# MxxxRow.net
KiCad netlist of a schematic drawn in EAGLE
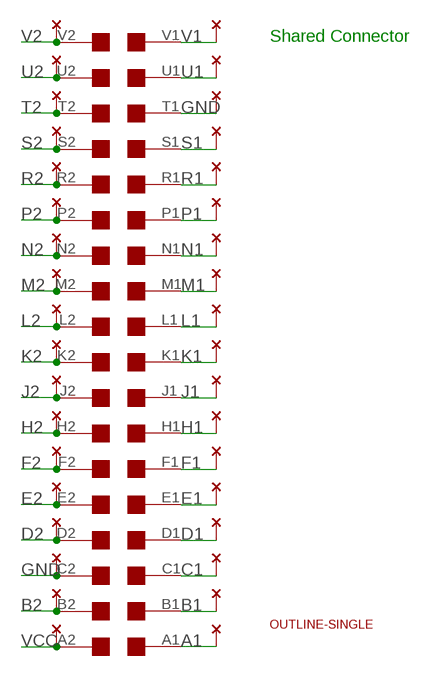
[diagram p0: schematic, sheet 1]
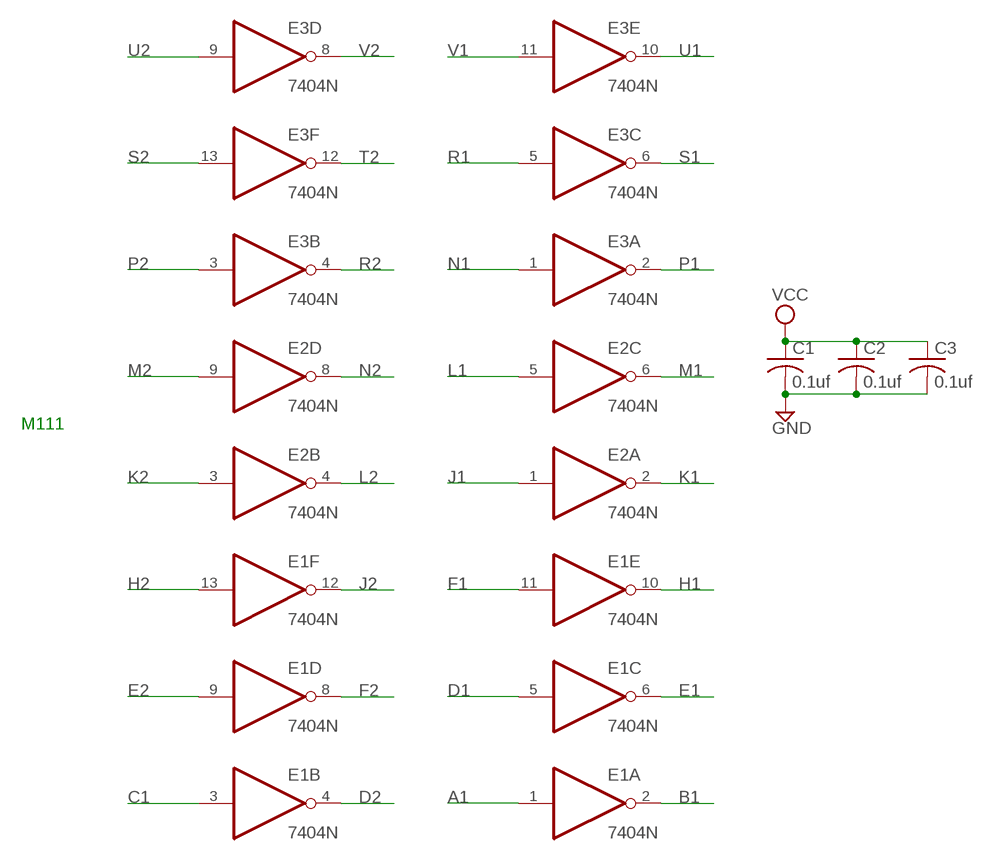
[diagram p1: schematic, sheet 2]
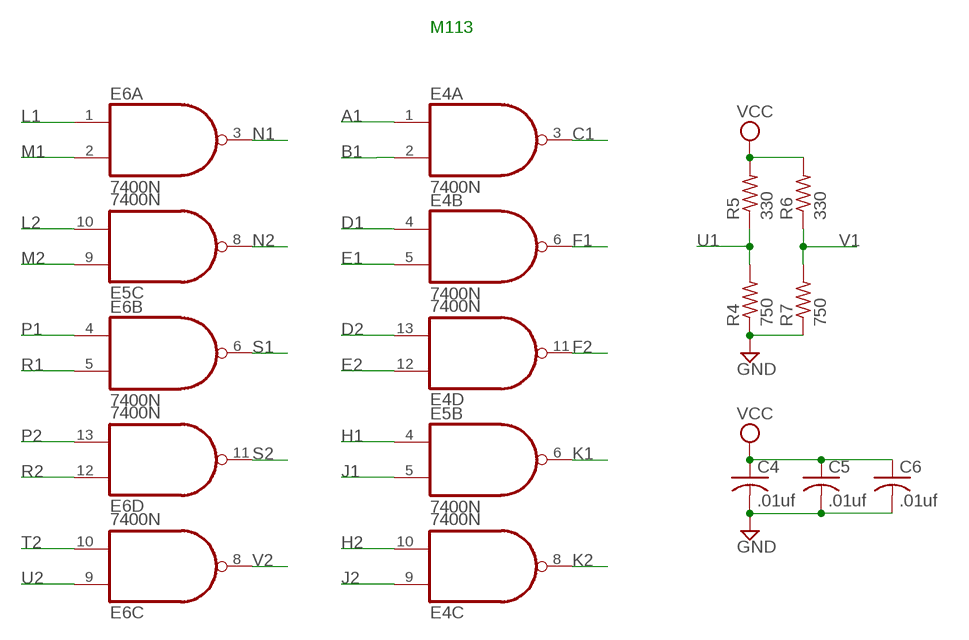
[diagram p2: schematic, sheet 3]
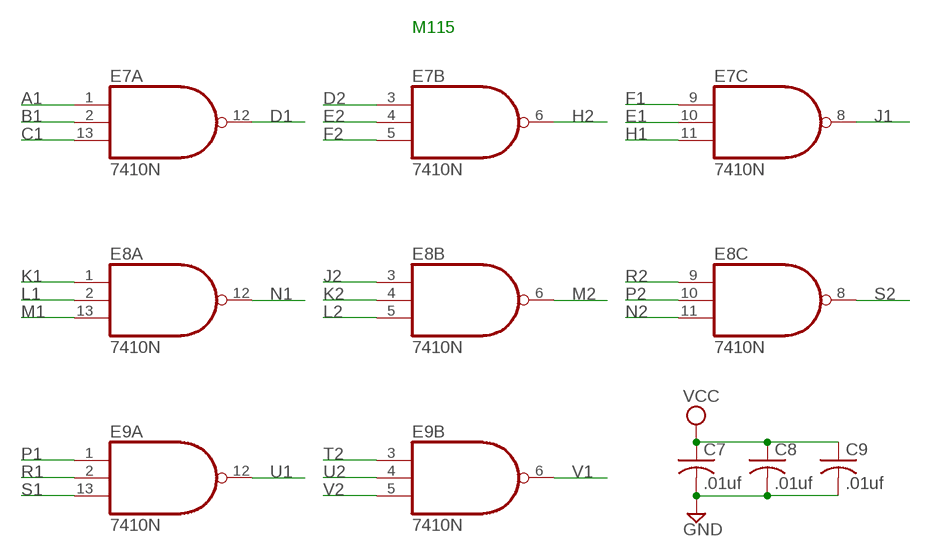
[diagram p3: schematic, sheet 4]
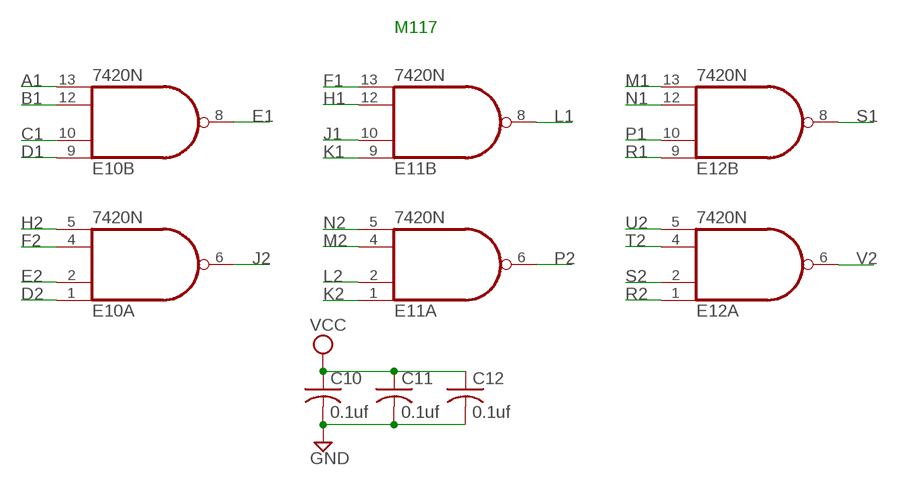
[diagram p4: schematic, sheet 5]
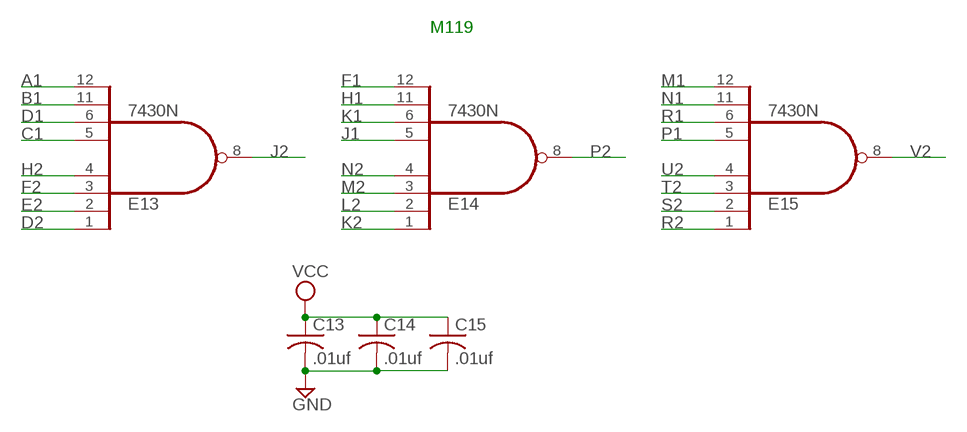
[diagram p5: schematic, sheet 6]

(export (version "E")
  (design (tool "Eeschema 10.0.6"))
  (components
    (comp (ref "C1")
      (value "0.1uf")
      (footprint "eagle-import:C050-025X075")
      (libsource (lib "eagle-import") (part "C-US050-025X075"))
    )
    (comp (ref "C2")
      (value "0.1uf")
      (footprint "eagle-import:C050-025X075")
      (libsource (lib "eagle-import") (part "C-US050-025X075"))
    )
    (comp (ref "C3")
      (value "0.1uf")
      (footprint "eagle-import:C050-025X075")
      (libsource (lib "eagle-import") (part "C-US050-025X075"))
    )
    (comp (ref "E1")
      (value "7404N")
      (footprint "eagle-import:DIL14")
      (libsource (lib "eagle-import") (part "7404N"))
    )
    (comp (ref "E2")
      (value "7404N")
      (footprint "eagle-import:DIL14")
      (libsource (lib "eagle-import") (part "7404N"))
    )
    (comp (ref "E3")
      (value "7404N")
      (footprint "eagle-import:DIL14")
      (libsource (lib "eagle-import") (part "7404N"))
    )
    (comp (ref "C13")
      (value ".01uf")
      (footprint "eagle-import:C050-025X075")
      (libsource (lib "eagle-import") (part "C-US050-025X075"))
    )
    (comp (ref "C14")
      (value ".01uf")
      (footprint "eagle-import:C050-025X075")
      (libsource (lib "eagle-import") (part "C-US050-025X075"))
    )
    (comp (ref "C15")
      (value ".01uf")
      (footprint "eagle-import:C050-025X075")
      (libsource (lib "eagle-import") (part "C-US050-025X075"))
    )
    (comp (ref "E13")
      (value "7430N")
      (footprint "eagle-import:DIL14")
      (libsource (lib "eagle-import") (part "7430N"))
    )
    (comp (ref "E14")
      (value "7430N")
      (footprint "eagle-import:DIL14")
      (libsource (lib "eagle-import") (part "7430N"))
    )
    (comp (ref "E15")
      (value "7430N")
      (footprint "eagle-import:DIL14")
      (libsource (lib "eagle-import") (part "7430N"))
    )
    (comp (ref "C4")
      (value ".01uf")
      (footprint "eagle-import:C050-025X075")
      (libsource (lib "eagle-import") (part "C-US050-025X075"))
    )
    (comp (ref "C5")
      (value ".01uf")
      (footprint "eagle-import:C050-025X075")
      (libsource (lib "eagle-import") (part "C-US050-025X075"))
    )
    (comp (ref "C6")
      (value ".01uf")
      (footprint "eagle-import:C050-025X075")
      (libsource (lib "eagle-import") (part "C-US050-025X075"))
    )
    (comp (ref "E4")
      (value "7400N")
      (footprint "eagle-import:DIL14")
      (libsource (lib "eagle-import") (part "7400N"))
    )
    (comp (ref "E5")
      (value "7400N")
      (footprint "eagle-import:DIL14")
      (libsource (lib "eagle-import") (part "7400N"))
    )
    (comp (ref "E6")
      (value "7400N")
      (footprint "eagle-import:DIL14")
      (libsource (lib "eagle-import") (part "7400N"))
    )
    (comp (ref "R4")
      (value "750")
      (footprint "eagle-import:0207_10")
      (libsource (lib "eagle-import") (part "R-US_0207/10"))
    )
    (comp (ref "R5")
      (value "330")
      (footprint "eagle-import:0207_10")
      (libsource (lib "eagle-import") (part "R-US_0207/10"))
    )
    (comp (ref "R6")
      (value "330")
      (footprint "eagle-import:0207_10")
      (libsource (lib "eagle-import") (part "R-US_0207/10"))
    )
    (comp (ref "R7")
      (value "750")
      (footprint "eagle-import:0207_10")
      (libsource (lib "eagle-import") (part "R-US_0207/10"))
    )
    (comp (ref "C7")
      (value ".01uf")
      (footprint "eagle-import:C050-025X075")
      (libsource (lib "eagle-import") (part "C-US050-025X075"))
    )
    (comp (ref "C8")
      (value ".01uf")
      (footprint "eagle-import:C050-025X075")
      (libsource (lib "eagle-import") (part "C-US050-025X075"))
    )
    (comp (ref "C9")
      (value ".01uf")
      (footprint "eagle-import:C050-025X075")
      (libsource (lib "eagle-import") (part "C-US050-025X075"))
    )
    (comp (ref "E7")
      (value "7410N")
      (footprint "eagle-import:DIL14")
      (libsource (lib "eagle-import") (part "7410N"))
    )
    (comp (ref "E8")
      (value "7410N")
      (footprint "eagle-import:DIL14")
      (libsource (lib "eagle-import") (part "7410N"))
    )
    (comp (ref "E9")
      (value "7410N")
      (footprint "eagle-import:DIL14")
      (libsource (lib "eagle-import") (part "7410N"))
    )
    (comp (ref "U$1")
      (value "EDGE-2CONNECTOR")
      (footprint "eagle-import:EDGE-CON2")
      (libsource (lib "eagle-import") (part "EDGE-2CONNECTOR"))
    )
    (comp (ref "U$4")
      (value "THRU-HOLE2A")
      (footprint "eagle-import:THRU-HOLEA")
      (libsource (lib "eagle-import") (part "THRU-HOLE2A"))
    )
    (comp (ref "U$5")
      (value "OUTLINE-SINGLE")
      (footprint "eagle-import:SINGLE")
      (libsource (lib "eagle-import") (part "OUTLINE-SINGLE"))
    )
    (comp (ref "C10")
      (value "0.1uf")
      (footprint "eagle-import:C050-025X075")
      (libsource (lib "eagle-import") (part "C-US050-025X075"))
    )
    (comp (ref "C11")
      (value "0.1uf")
      (footprint "eagle-import:C050-025X075")
      (libsource (lib "eagle-import") (part "C-US050-025X075"))
    )
    (comp (ref "C12")
      (value "0.1uf")
      (footprint "eagle-import:C050-025X075")
      (libsource (lib "eagle-import") (part "C-US050-025X075"))
    )
    (comp (ref "E10")
      (value "7420N")
      (footprint "eagle-import:DIL14")
      (libsource (lib "eagle-import") (part "7420NS"))
    )
    (comp (ref "E11")
      (value "7420N")
      (footprint "eagle-import:DIL14")
      (libsource (lib "eagle-import") (part "7420NS"))
    )
    (comp (ref "E12")
      (value "7420N")
      (footprint "eagle-import:DIL14")
      (libsource (lib "eagle-import") (part "7420NS"))
    )
  )
  (nets
    (net (code "1") (name "A1") (class "Default")
      (node (ref "E1") (pin "1") (pinfunction "I_1") (pintype "input"))
      (node (ref "E10") (pin "13") (pinfunction "I3_13") (pintype "input"))
      (node (ref "E13") (pin "12") (pinfunction "I7_12") (pintype "input"))
      (node (ref "E4") (pin "1") (pinfunction "I0_1") (pintype "input"))
      (node (ref "E7") (pin "1") (pinfunction "I0_1") (pintype "input"))
      (node (ref "U$1") (pin "A1") (pinfunction "1_A1") (pintype "bidirectional"))
      (node (ref "U$4") (pin "A1") (pinfunction "P$1_A1") (pintype "passive"))
    )
    (net (code "2") (name "B1") (class "Default")
      (node (ref "E1") (pin "2") (pinfunction "O_2") (pintype "output"))
      (node (ref "E10") (pin "12") (pinfunction "I2_12") (pintype "input"))
      (node (ref "E13") (pin "11") (pinfunction "I6_11") (pintype "input"))
      (node (ref "E4") (pin "2") (pinfunction "I1_2") (pintype "input"))
      (node (ref "E7") (pin "2") (pinfunction "I1_2") (pintype "input"))
      (node (ref "U$1") (pin "B1") (pinfunction "1_B1") (pintype "bidirectional"))
      (node (ref "U$4") (pin "B1") (pinfunction "P$1_B1") (pintype "passive"))
    )
    (net (code "3") (name "B2") (class "Default")
      (node (ref "U$1") (pin "B2") (pinfunction "1_B2") (pintype "bidirectional"))
      (node (ref "U$4") (pin "B2") (pinfunction "P$1_B2") (pintype "passive"))
    )
    (net (code "4") (name "C1") (class "Default")
      (node (ref "E1") (pin "3") (pinfunction "I_3") (pintype "input"))
      (node (ref "E10") (pin "10") (pinfunction "I1_10") (pintype "input"))
      (node (ref "E13") (pin "5") (pinfunction "I4_5") (pintype "input"))
      (node (ref "E4") (pin "3") (pinfunction "O_3") (pintype "output"))
      (node (ref "E7") (pin "13") (pinfunction "I2_13") (pintype "input"))
      (node (ref "U$1") (pin "C1") (pinfunction "1_C1") (pintype "bidirectional"))
      (node (ref "U$4") (pin "C1") (pinfunction "P$1_C1") (pintype "passive"))
    )
    (net (code "5") (name "D1") (class "Default")
      (node (ref "E1") (pin "5") (pinfunction "I_5") (pintype "input"))
      (node (ref "E10") (pin "9") (pinfunction "I0_9") (pintype "input"))
      (node (ref "E13") (pin "6") (pinfunction "I5_6") (pintype "input"))
      (node (ref "E4") (pin "4") (pinfunction "I0_4") (pintype "input"))
      (node (ref "E7") (pin "12") (pinfunction "O_12") (pintype "output"))
      (node (ref "U$1") (pin "D1") (pinfunction "1_D1") (pintype "bidirectional"))
      (node (ref "U$4") (pin "D1") (pinfunction "P$1_D1") (pintype "passive"))
    )
    (net (code "6") (name "D2") (class "Default")
      (node (ref "E1") (pin "4") (pinfunction "O_4") (pintype "output"))
      (node (ref "E10") (pin "1") (pinfunction "I0_1") (pintype "input"))
      (node (ref "E13") (pin "1") (pinfunction "I0_1") (pintype "input"))
      (node (ref "E4") (pin "13") (pinfunction "I1_13") (pintype "input"))
      (node (ref "E7") (pin "3") (pinfunction "I0_3") (pintype "input"))
      (node (ref "U$1") (pin "D2") (pinfunction "1_D2") (pintype "bidirectional"))
      (node (ref "U$4") (pin "D2") (pinfunction "P$1_D2") (pintype "passive"))
    )
    (net (code "7") (name "E1") (class "Default")
      (node (ref "E1") (pin "6") (pinfunction "O_6") (pintype "output"))
      (node (ref "E10") (pin "8") (pinfunction "O_8") (pintype "output"))
      (node (ref "E4") (pin "5") (pinfunction "I1_5") (pintype "input"))
      (node (ref "E7") (pin "10") (pinfunction "I1_10") (pintype "input"))
      (node (ref "U$1") (pin "E1") (pinfunction "1_E1") (pintype "bidirectional"))
      (node (ref "U$4") (pin "E1") (pinfunction "P$1_E1") (pintype "passive"))
    )
    (net (code "8") (name "E2") (class "Default")
      (node (ref "E1") (pin "9") (pinfunction "I_9") (pintype "input"))
      (node (ref "E10") (pin "2") (pinfunction "I1_2") (pintype "input"))
      (node (ref "E13") (pin "2") (pinfunction "I1_2") (pintype "input"))
      (node (ref "E4") (pin "12") (pinfunction "I0_12") (pintype "input"))
      (node (ref "E7") (pin "4") (pinfunction "I1_4") (pintype "input"))
      (node (ref "U$1") (pin "E2") (pinfunction "1_E2") (pintype "bidirectional"))
      (node (ref "U$4") (pin "E2") (pinfunction "P$1_E2") (pintype "passive"))
    )
    (net (code "9") (name "F1") (class "Default")
      (node (ref "E1") (pin "11") (pinfunction "I_11") (pintype "input"))
      (node (ref "E11") (pin "13") (pinfunction "I3_13") (pintype "input"))
      (node (ref "E14") (pin "12") (pinfunction "I7_12") (pintype "input"))
      (node (ref "E4") (pin "6") (pinfunction "O_6") (pintype "output"))
      (node (ref "E7") (pin "9") (pinfunction "I0_9") (pintype "input"))
      (node (ref "U$1") (pin "F1") (pinfunction "1_F1") (pintype "bidirectional"))
      (node (ref "U$4") (pin "F1") (pinfunction "P$1_F1") (pintype "passive"))
    )
    (net (code "10") (name "F2") (class "Default")
      (node (ref "E1") (pin "8") (pinfunction "O_8") (pintype "output"))
      (node (ref "E10") (pin "4") (pinfunction "I2_4") (pintype "input"))
      (node (ref "E13") (pin "3") (pinfunction "I2_3") (pintype "input"))
      (node (ref "E4") (pin "11") (pinfunction "O_11") (pintype "output"))
      (node (ref "E7") (pin "5") (pinfunction "I2_5") (pintype "input"))
      (node (ref "U$1") (pin "F2") (pinfunction "1_F2") (pintype "bidirectional"))
      (node (ref "U$4") (pin "F2") (pinfunction "P$1_F2") (pintype "passive"))
    )
    (net (code "11") (name "GND") (class "Default")
      (node (ref "C1") (pin "2") (pinfunction "2_2") (pintype "passive"))
      (node (ref "C10") (pin "2") (pinfunction "2_2") (pintype "passive"))
      (node (ref "C11") (pin "2") (pinfunction "2_2") (pintype "passive"))
      (node (ref "C12") (pin "2") (pinfunction "2_2") (pintype "passive"))
      (node (ref "C13") (pin "2") (pinfunction "2_2") (pintype "passive"))
      (node (ref "C14") (pin "2") (pinfunction "2_2") (pintype "passive"))
      (node (ref "C15") (pin "2") (pinfunction "2_2") (pintype "passive"))
      (node (ref "C2") (pin "2") (pinfunction "2_2") (pintype "passive"))
      (node (ref "C3") (pin "2") (pinfunction "2_2") (pintype "passive"))
      (node (ref "C4") (pin "2") (pinfunction "2_2") (pintype "passive"))
      (node (ref "C5") (pin "2") (pinfunction "2_2") (pintype "passive"))
      (node (ref "C6") (pin "2") (pinfunction "2_2") (pintype "passive"))
      (node (ref "C7") (pin "2") (pinfunction "2_2") (pintype "passive"))
      (node (ref "C8") (pin "2") (pinfunction "2_2") (pintype "passive"))
      (node (ref "C9") (pin "2") (pinfunction "2_2") (pintype "passive"))
      (node (ref "R4") (pin "1") (pinfunction "1_1") (pintype "passive"))
      (node (ref "R7") (pin "1") (pinfunction "1_1") (pintype "passive"))
      (node (ref "U$1") (pin "C2") (pinfunction "1_C2") (pintype "bidirectional"))
      (node (ref "U$1") (pin "T1") (pinfunction "1_T1") (pintype "bidirectional"))
      (node (ref "U$4") (pin "C2") (pinfunction "P$1_C2") (pintype "passive"))
      (node (ref "U$4") (pin "T1") (pinfunction "P$1_T1") (pintype "passive"))
    )
    (net (code "12") (name "H1") (class "Default")
      (node (ref "E1") (pin "10") (pinfunction "O_10") (pintype "output"))
      (node (ref "E11") (pin "12") (pinfunction "I2_12") (pintype "input"))
      (node (ref "E14") (pin "11") (pinfunction "I6_11") (pintype "input"))
      (node (ref "E5") (pin "4") (pinfunction "I0_4") (pintype "input"))
      (node (ref "E7") (pin "11") (pinfunction "I2_11") (pintype "input"))
      (node (ref "U$1") (pin "H1") (pinfunction "1_H1") (pintype "bidirectional"))
      (node (ref "U$4") (pin "H1") (pinfunction "P$1_H1") (pintype "passive"))
    )
    (net (code "13") (name "H2") (class "Default")
      (node (ref "E1") (pin "13") (pinfunction "I_13") (pintype "input"))
      (node (ref "E10") (pin "5") (pinfunction "I3_5") (pintype "input"))
      (node (ref "E13") (pin "4") (pinfunction "I3_4") (pintype "input"))
      (node (ref "E4") (pin "10") (pinfunction "I1_10") (pintype "input"))
      (node (ref "E7") (pin "6") (pinfunction "O_6") (pintype "output"))
      (node (ref "U$1") (pin "H2") (pinfunction "1_H2") (pintype "bidirectional"))
      (node (ref "U$4") (pin "H2") (pinfunction "P$1_H2") (pintype "passive"))
    )
    (net (code "14") (name "J1") (class "Default")
      (node (ref "E11") (pin "10") (pinfunction "I1_10") (pintype "input"))
      (node (ref "E14") (pin "5") (pinfunction "I4_5") (pintype "input"))
      (node (ref "E2") (pin "1") (pinfunction "I_1") (pintype "input"))
      (node (ref "E5") (pin "5") (pinfunction "I1_5") (pintype "input"))
      (node (ref "E7") (pin "8") (pinfunction "O_8") (pintype "output"))
      (node (ref "U$1") (pin "J1") (pinfunction "1_J1") (pintype "bidirectional"))
      (node (ref "U$4") (pin "J1") (pinfunction "P$1_J1") (pintype "passive"))
    )
    (net (code "15") (name "J2") (class "Default")
      (node (ref "E1") (pin "12") (pinfunction "O_12") (pintype "output"))
      (node (ref "E10") (pin "6") (pinfunction "O_6") (pintype "output"))
      (node (ref "E13") (pin "8") (pinfunction "O_8") (pintype "output"))
      (node (ref "E4") (pin "9") (pinfunction "I0_9") (pintype "input"))
      (node (ref "E8") (pin "3") (pinfunction "I0_3") (pintype "input"))
      (node (ref "U$1") (pin "J2") (pinfunction "1_J2") (pintype "bidirectional"))
      (node (ref "U$4") (pin "J2") (pinfunction "P$1_J2") (pintype "passive"))
    )
    (net (code "16") (name "K1") (class "Default")
      (node (ref "E11") (pin "9") (pinfunction "I0_9") (pintype "input"))
      (node (ref "E14") (pin "6") (pinfunction "I5_6") (pintype "input"))
      (node (ref "E2") (pin "2") (pinfunction "O_2") (pintype "output"))
      (node (ref "E5") (pin "6") (pinfunction "O_6") (pintype "output"))
      (node (ref "E8") (pin "1") (pinfunction "I0_1") (pintype "input"))
      (node (ref "U$1") (pin "K1") (pinfunction "1_K1") (pintype "bidirectional"))
      (node (ref "U$4") (pin "K1") (pinfunction "P$1_K1") (pintype "passive"))
    )
    (net (code "17") (name "K2") (class "Default")
      (node (ref "E11") (pin "1") (pinfunction "I0_1") (pintype "input"))
      (node (ref "E14") (pin "1") (pinfunction "I0_1") (pintype "input"))
      (node (ref "E2") (pin "3") (pinfunction "I_3") (pintype "input"))
      (node (ref "E4") (pin "8") (pinfunction "O_8") (pintype "output"))
      (node (ref "E8") (pin "4") (pinfunction "I1_4") (pintype "input"))
      (node (ref "U$1") (pin "K2") (pinfunction "1_K2") (pintype "bidirectional"))
      (node (ref "U$4") (pin "K2") (pinfunction "P$1_K2") (pintype "passive"))
    )
    (net (code "18") (name "L1") (class "Default")
      (node (ref "E11") (pin "8") (pinfunction "O_8") (pintype "output"))
      (node (ref "E2") (pin "5") (pinfunction "I_5") (pintype "input"))
      (node (ref "E6") (pin "1") (pinfunction "I0_1") (pintype "input"))
      (node (ref "E8") (pin "2") (pinfunction "I1_2") (pintype "input"))
      (node (ref "U$1") (pin "L1") (pinfunction "1_L1") (pintype "bidirectional"))
      (node (ref "U$4") (pin "L1") (pinfunction "P$1_L1") (pintype "passive"))
    )
    (net (code "19") (name "L2") (class "Default")
      (node (ref "E11") (pin "2") (pinfunction "I1_2") (pintype "input"))
      (node (ref "E14") (pin "2") (pinfunction "I1_2") (pintype "input"))
      (node (ref "E2") (pin "4") (pinfunction "O_4") (pintype "output"))
      (node (ref "E5") (pin "10") (pinfunction "I1_10") (pintype "input"))
      (node (ref "E8") (pin "5") (pinfunction "I2_5") (pintype "input"))
      (node (ref "U$1") (pin "L2") (pinfunction "1_L2") (pintype "bidirectional"))
      (node (ref "U$4") (pin "L2") (pinfunction "P$1_L2") (pintype "passive"))
    )
    (net (code "20") (name "M1") (class "Default")
      (node (ref "E12") (pin "13") (pinfunction "I3_13") (pintype "input"))
      (node (ref "E15") (pin "12") (pinfunction "I7_12") (pintype "input"))
      (node (ref "E2") (pin "6") (pinfunction "O_6") (pintype "output"))
      (node (ref "E6") (pin "2") (pinfunction "I1_2") (pintype "input"))
      (node (ref "E8") (pin "13") (pinfunction "I2_13") (pintype "input"))
      (node (ref "U$1") (pin "M1") (pinfunction "1_M1") (pintype "bidirectional"))
      (node (ref "U$4") (pin "M1") (pinfunction "P$1_M1") (pintype "passive"))
    )
    (net (code "21") (name "M2") (class "Default")
      (node (ref "E11") (pin "4") (pinfunction "I2_4") (pintype "input"))
      (node (ref "E14") (pin "3") (pinfunction "I2_3") (pintype "input"))
      (node (ref "E2") (pin "9") (pinfunction "I_9") (pintype "input"))
      (node (ref "E5") (pin "9") (pinfunction "I0_9") (pintype "input"))
      (node (ref "E8") (pin "6") (pinfunction "O_6") (pintype "output"))
      (node (ref "U$1") (pin "M2") (pinfunction "1_M2") (pintype "bidirectional"))
      (node (ref "U$4") (pin "M2") (pinfunction "P$1_M2") (pintype "passive"))
    )
    (net (code "22") (name "N1") (class "Default")
      (node (ref "E12") (pin "12") (pinfunction "I2_12") (pintype "input"))
      (node (ref "E15") (pin "11") (pinfunction "I6_11") (pintype "input"))
      (node (ref "E3") (pin "1") (pinfunction "I_1") (pintype "input"))
      (node (ref "E6") (pin "3") (pinfunction "O_3") (pintype "output"))
      (node (ref "E8") (pin "12") (pinfunction "O_12") (pintype "output"))
      (node (ref "U$1") (pin "N1") (pinfunction "1_N1") (pintype "bidirectional"))
      (node (ref "U$4") (pin "N1") (pinfunction "P$1_N1") (pintype "passive"))
    )
    (net (code "23") (name "N2") (class "Default")
      (node (ref "E11") (pin "5") (pinfunction "I3_5") (pintype "input"))
      (node (ref "E14") (pin "4") (pinfunction "I3_4") (pintype "input"))
      (node (ref "E2") (pin "8") (pinfunction "O_8") (pintype "output"))
      (node (ref "E5") (pin "8") (pinfunction "O_8") (pintype "output"))
      (node (ref "E8") (pin "11") (pinfunction "I2_11") (pintype "input"))
      (node (ref "U$1") (pin "N2") (pinfunction "1_N2") (pintype "bidirectional"))
      (node (ref "U$4") (pin "N2") (pinfunction "P$1_N2") (pintype "passive"))
    )
    (net (code "24") (name "P1") (class "Default")
      (node (ref "E12") (pin "10") (pinfunction "I1_10") (pintype "input"))
      (node (ref "E15") (pin "5") (pinfunction "I4_5") (pintype "input"))
      (node (ref "E3") (pin "2") (pinfunction "O_2") (pintype "output"))
      (node (ref "E6") (pin "4") (pinfunction "I0_4") (pintype "input"))
      (node (ref "E9") (pin "1") (pinfunction "I0_1") (pintype "input"))
      (node (ref "U$1") (pin "P1") (pinfunction "1_P1") (pintype "bidirectional"))
      (node (ref "U$4") (pin "P1") (pinfunction "P$1_P1") (pintype "passive"))
    )
    (net (code "25") (name "P2") (class "Default")
      (node (ref "E11") (pin "6") (pinfunction "O_6") (pintype "output"))
      (node (ref "E14") (pin "8") (pinfunction "O_8") (pintype "output"))
      (node (ref "E3") (pin "3") (pinfunction "I_3") (pintype "input"))
      (node (ref "E6") (pin "13") (pinfunction "I1_13") (pintype "input"))
      (node (ref "E8") (pin "10") (pinfunction "I1_10") (pintype "input"))
      (node (ref "U$1") (pin "P2") (pinfunction "1_P2") (pintype "bidirectional"))
      (node (ref "U$4") (pin "P2") (pinfunction "P$1_P2") (pintype "passive"))
    )
    (net (code "26") (name "R1") (class "Default")
      (node (ref "E12") (pin "9") (pinfunction "I0_9") (pintype "input"))
      (node (ref "E15") (pin "6") (pinfunction "I5_6") (pintype "input"))
      (node (ref "E3") (pin "5") (pinfunction "I_5") (pintype "input"))
      (node (ref "E6") (pin "5") (pinfunction "I1_5") (pintype "input"))
      (node (ref "E9") (pin "2") (pinfunction "I1_2") (pintype "input"))
      (node (ref "U$1") (pin "R1") (pinfunction "1_R1") (pintype "bidirectional"))
      (node (ref "U$4") (pin "R1") (pinfunction "P$1_R1") (pintype "passive"))
    )
    (net (code "27") (name "R2") (class "Default")
      (node (ref "E12") (pin "1") (pinfunction "I0_1") (pintype "input"))
      (node (ref "E15") (pin "1") (pinfunction "I0_1") (pintype "input"))
      (node (ref "E3") (pin "4") (pinfunction "O_4") (pintype "output"))
      (node (ref "E6") (pin "12") (pinfunction "I0_12") (pintype "input"))
      (node (ref "E8") (pin "9") (pinfunction "I0_9") (pintype "input"))
      (node (ref "U$1") (pin "R2") (pinfunction "1_R2") (pintype "bidirectional"))
      (node (ref "U$4") (pin "R2") (pinfunction "P$1_R2") (pintype "passive"))
    )
    (net (code "28") (name "S1") (class "Default")
      (node (ref "E12") (pin "8") (pinfunction "O_8") (pintype "output"))
      (node (ref "E3") (pin "6") (pinfunction "O_6") (pintype "output"))
      (node (ref "E6") (pin "6") (pinfunction "O_6") (pintype "output"))
      (node (ref "E9") (pin "13") (pinfunction "I2_13") (pintype "input"))
      (node (ref "U$1") (pin "S1") (pinfunction "1_S1") (pintype "bidirectional"))
      (node (ref "U$4") (pin "S1") (pinfunction "P$1_S1") (pintype "passive"))
    )
    (net (code "29") (name "S2") (class "Default")
      (node (ref "E12") (pin "2") (pinfunction "I1_2") (pintype "input"))
      (node (ref "E15") (pin "2") (pinfunction "I1_2") (pintype "input"))
      (node (ref "E3") (pin "13") (pinfunction "I_13") (pintype "input"))
      (node (ref "E6") (pin "11") (pinfunction "O_11") (pintype "output"))
      (node (ref "E8") (pin "8") (pinfunction "O_8") (pintype "output"))
      (node (ref "U$1") (pin "S2") (pinfunction "1_S2") (pintype "bidirectional"))
      (node (ref "U$4") (pin "S2") (pinfunction "P$1_S2") (pintype "passive"))
    )
    (net (code "30") (name "T2") (class "Default")
      (node (ref "E12") (pin "4") (pinfunction "I2_4") (pintype "input"))
      (node (ref "E15") (pin "3") (pinfunction "I2_3") (pintype "input"))
      (node (ref "E3") (pin "12") (pinfunction "O_12") (pintype "output"))
      (node (ref "E6") (pin "10") (pinfunction "I1_10") (pintype "input"))
      (node (ref "E9") (pin "3") (pinfunction "I0_3") (pintype "input"))
      (node (ref "U$1") (pin "T2") (pinfunction "1_T2") (pintype "bidirectional"))
      (node (ref "U$4") (pin "T2") (pinfunction "P$1_T2") (pintype "passive"))
    )
    (net (code "31") (name "U1") (class "Default")
      (node (ref "E3") (pin "10") (pinfunction "O_10") (pintype "output"))
      (node (ref "E9") (pin "12") (pinfunction "O_12") (pintype "output"))
      (node (ref "R4") (pin "2") (pinfunction "2_2") (pintype "passive"))
      (node (ref "R5") (pin "1") (pinfunction "1_1") (pintype "passive"))
      (node (ref "U$1") (pin "U1") (pinfunction "1_U1") (pintype "bidirectional"))
      (node (ref "U$4") (pin "U1") (pinfunction "P$1_U1") (pintype "passive"))
    )
    (net (code "32") (name "U2") (class "Default")
      (node (ref "E12") (pin "5") (pinfunction "I3_5") (pintype "input"))
      (node (ref "E15") (pin "4") (pinfunction "I3_4") (pintype "input"))
      (node (ref "E3") (pin "9") (pinfunction "I_9") (pintype "input"))
      (node (ref "E6") (pin "9") (pinfunction "I0_9") (pintype "input"))
      (node (ref "E9") (pin "4") (pinfunction "I1_4") (pintype "input"))
      (node (ref "U$1") (pin "U2") (pinfunction "1_U2") (pintype "bidirectional"))
      (node (ref "U$4") (pin "U2") (pinfunction "P$1_U2") (pintype "passive"))
    )
    (net (code "33") (name "V1") (class "Default")
      (node (ref "E3") (pin "11") (pinfunction "I_11") (pintype "input"))
      (node (ref "E9") (pin "6") (pinfunction "O_6") (pintype "output"))
      (node (ref "R6") (pin "1") (pinfunction "1_1") (pintype "passive"))
      (node (ref "R7") (pin "2") (pinfunction "2_2") (pintype "passive"))
      (node (ref "U$1") (pin "V1") (pinfunction "1_V1") (pintype "bidirectional"))
      (node (ref "U$4") (pin "V1") (pinfunction "P$1_V1") (pintype "passive"))
    )
    (net (code "34") (name "V2") (class "Default")
      (node (ref "E12") (pin "6") (pinfunction "O_6") (pintype "output"))
      (node (ref "E15") (pin "8") (pinfunction "O_8") (pintype "output"))
      (node (ref "E3") (pin "8") (pinfunction "O_8") (pintype "output"))
      (node (ref "E6") (pin "8") (pinfunction "O_8") (pintype "output"))
      (node (ref "E9") (pin "5") (pinfunction "I2_5") (pintype "input"))
      (node (ref "U$1") (pin "V2") (pinfunction "1_V2") (pintype "bidirectional"))
      (node (ref "U$4") (pin "V2") (pinfunction "P$1_V2") (pintype "passive"))
    )
    (net (code "35") (name "VCC") (class "Default")
      (node (ref "C1") (pin "1") (pinfunction "1_1") (pintype "passive"))
      (node (ref "C10") (pin "1") (pinfunction "1_1") (pintype "passive"))
      (node (ref "C11") (pin "1") (pinfunction "1_1") (pintype "passive"))
      (node (ref "C12") (pin "1") (pinfunction "1_1") (pintype "passive"))
      (node (ref "C13") (pin "1") (pinfunction "1_1") (pintype "passive"))
      (node (ref "C14") (pin "1") (pinfunction "1_1") (pintype "passive"))
      (node (ref "C15") (pin "1") (pinfunction "1_1") (pintype "passive"))
      (node (ref "C2") (pin "1") (pinfunction "1_1") (pintype "passive"))
      (node (ref "C3") (pin "1") (pinfunction "1_1") (pintype "passive"))
      (node (ref "C4") (pin "1") (pinfunction "1_1") (pintype "passive"))
      (node (ref "C5") (pin "1") (pinfunction "1_1") (pintype "passive"))
      (node (ref "C6") (pin "1") (pinfunction "1_1") (pintype "passive"))
      (node (ref "C7") (pin "1") (pinfunction "1_1") (pintype "passive"))
      (node (ref "C8") (pin "1") (pinfunction "1_1") (pintype "passive"))
      (node (ref "C9") (pin "1") (pinfunction "1_1") (pintype "passive"))
      (node (ref "R5") (pin "2") (pinfunction "2_2") (pintype "passive"))
      (node (ref "R6") (pin "2") (pinfunction "2_2") (pintype "passive"))
      (node (ref "U$1") (pin "A2") (pinfunction "1_A2") (pintype "bidirectional"))
      (node (ref "U$4") (pin "A2") (pinfunction "P$1_A2") (pintype "passive"))
    )
  )
)
